# POWER.net
KiCad netlist of a schematic drawn in Altium Designer
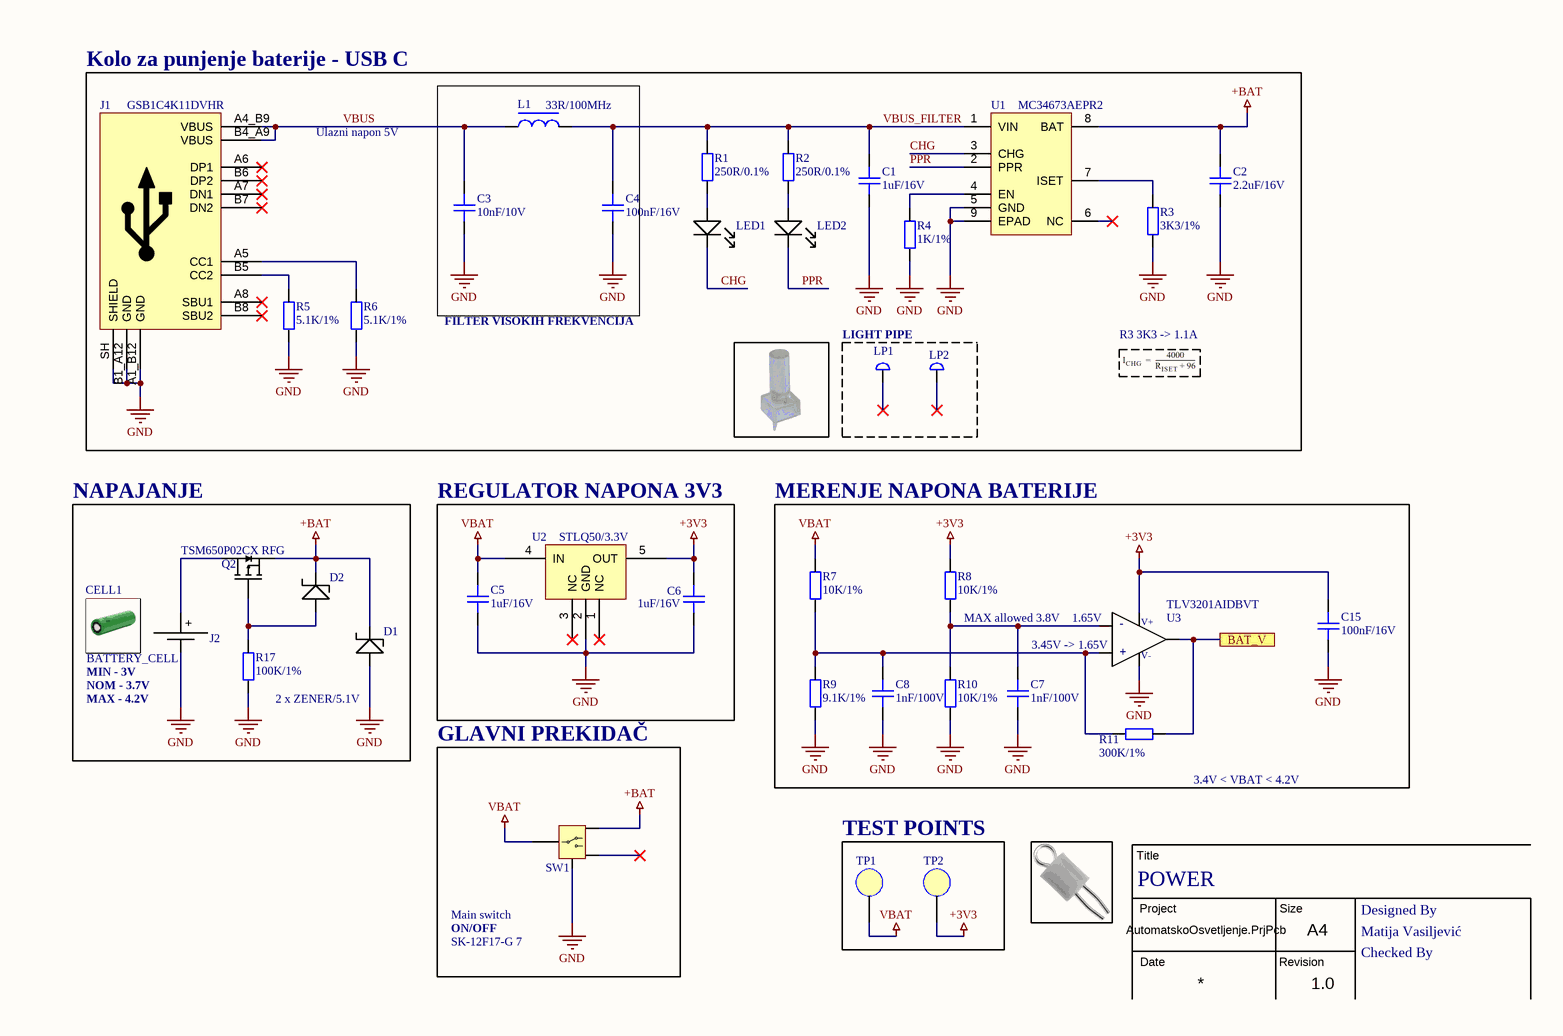
[diagram p0: POWER.SchDoc]

(export (version "E")
  (design (tool "Eeschema 10.0.6"))
  (components
    (comp (ref "C1")
      (value "1uF/16V")
      (footprint "CAP_0603")
      (description "1 µF ±5% 16V Ceramic Capacitor X7R 0603 (1608 Metric)")
      (fields (field (name "MPN") "0603YC105JAT2A"))
      (libsource (lib "Library-AutomatskoOsvetljenje") (part "1uF/16V"))
    )
    (comp (ref "C2")
      (value "2.2uF/16V")
      (footprint "CAP_0603")
      (description "2.2 µF ±10% 16V Ceramic Capacitor X7S 0603 (1608 Metric)")
      (fields (field (name "MPN") "GRM188C71C225KE11D"))
      (libsource (lib "Library-AutomatskoOsvetljenje") (part "2.2uF/16V"))
    )
    (comp (ref "C3")
      (value "10nF/10V")
      (footprint "CAP_0603")
      (description "10000 pF ±10% 50V Ceramic Capacitor X7R 0603 (1608 Metric)")
      (fields (field (name "MPN") "0603B103K500CT"))
      (libsource (lib "Library-AutomatskoOsvetljenje") (part "10nF/10V"))
    )
    (comp (ref "C4")
      (value "100nF/16V")
      (footprint "CAP_0603")
      (description "0.1 µF ±10% 16V Ceramic Capacitor X7R 0603 (1608 Metric)")
      (fields (field (name "MPN") "CC0603KRX7R7BB104"))
      (libsource (lib "Library-AutomatskoOsvetljenje") (part "100nF/16V"))
    )
    (comp (ref "C5")
      (value "1uF/16V")
      (footprint "CAP_0603")
      (description "1 µF ±5% 16V Ceramic Capacitor X7R 0603 (1608 Metric)")
      (fields (field (name "MPN") "0603YC105JAT2A"))
      (libsource (lib "Library-AutomatskoOsvetljenje") (part "1uF/16V"))
    )
    (comp (ref "C6")
      (value "1uF/16V")
      (footprint "CAP_0603")
      (description "1 µF ±5% 16V Ceramic Capacitor X7R 0603 (1608 Metric)")
      (fields (field (name "MPN") "0603YC105JAT2A"))
      (libsource (lib "Library-AutomatskoOsvetljenje") (part "1uF/16V"))
    )
    (comp (ref "C7")
      (value "1nF/100V")
      (footprint "CAP_0603")
      (description "1 µF ±10% 10V Ceramic Capacitor X7R 0603 (1608 Metric)")
      (fields (field (name "MPN") "CL10B105KP8NNNC"))
      (libsource (lib "Library-AutomatskoOsvetljenje") (part "1nF/100V"))
    )
    (comp (ref "C8")
      (value "1nF/100V")
      (footprint "CAP_0603")
      (description "1 µF ±10% 10V Ceramic Capacitor X7R 0603 (1608 Metric)")
      (fields (field (name "MPN") "CL10B105KP8NNNC"))
      (libsource (lib "Library-AutomatskoOsvetljenje") (part "1nF/100V"))
    )
    (comp (ref "C15")
      (value "100nF/16V")
      (footprint "CAP_0603")
      (description "0.1 µF ±10% 16V Ceramic Capacitor X7R 0603 (1608 Metric)")
      (fields (field (name "MPN") "CC0603KRX7R7BB104"))
      (libsource (lib "Library-AutomatskoOsvetljenje") (part "100nF/16V"))
    )
    (comp (ref "CELL1")
      (value "BATTERY_CELL")
      (description "CELL 18650 SAMSUNG 3200mAh")
      (libsource (lib "Library-AutomatskoOsvetljenje") (part "BATTERY_CELL"))
    )
    (comp (ref "D1")
      (value "ZENER/5.1V")
      (footprint "ZENER_SMA")
      (description "Zener Diode 5.1 V 1.5 W ±5% Surface Mount SMA")
      (fields (field (name "MPN") "1SMA5918BT3G"))
      (libsource (lib "Library-AutomatskoOsvetljenje") (part "ZENER/5.1V"))
    )
    (comp (ref "D2")
      (value "2 x ZENER/5.1V")
      (footprint "ZENER_SMA")
      (description "Zener Diode 5.1 V 1.5 W ±5% Surface Mount SMA")
      (fields (field (name "MPN") "1SMA5918BT3G"))
      (libsource (lib "Library-AutomatskoOsvetljenje") (part "ZENER/5.1V"))
    )
    (comp (ref "J1")
      (value "GSB1C4K11DVHR")
      (footprint "USBC_GSB1C4K11DVHR")
      (description "USB-C (USB TYPE-C) USB 2.0 Receptacle Connector 24 (16+8 Dummy) Position Through Hole, Right Angle")
      (libsource (lib "Library-AutomatskoOsvetljenje") (part "USB_C_GSB1C4K11DVHR"))
    )
    (comp (ref "J2")
      (value "12BHC186CLP-GR")
      (footprint "BATTERY_HOLDER_18650")
      (description "Cylindrical Battery Contacts, Clips, Holders & Springs 18650 Holder Board Mount Clip")
      (libsource (lib "Library-AutomatskoOsvetljenje") (part "BATTERY_HOLDER_18650"))
    )
    (comp (ref "L1")
      (value "33R/100MHz")
      (footprint "INDC_0603")
      (description "33 Ohms @ 100 MHz 1 Power Line Ferrite Bead 0603 (1608 Metric) 3A 25mOhm")
      (fields (field (name "MPN") "BLM18PG330SN1DBLM18PG330SN1D"))
      (libsource (lib "Library-AutomatskoOsvetljenje") (part "33R/100MHz"))
    )
    (comp (ref "LED1")
      (value "150060RS75000")
      (footprint "LED_0603")
      (description "Red 625nm LED Indication - Discrete 2V 0603 (1608 Metric)")
      (libsource (lib "Library-AutomatskoOsvetljenje") (part "INDICATION_LED_RED_1500_1"))
    )
    (comp (ref "LED2")
      (value "150060VS75000")
      (footprint "LED_0603")
      (description "Green 570nm LED Indication - Discrete 2V 0603 (1608 Metric)")
      (libsource (lib "Library-AutomatskoOsvetljenje") (part "INDICATION_LED_GREEN_1500"))
    )
    (comp (ref "LP1")
      (value "LIGHT_PIPE")
      (footprint "LIGHT_PIPE_VLP-400-F")
      (description "Light pipe for indication led")
      (fields (field (name "MPN") "VLP-400-F"))
      (libsource (lib "Library-AutomatskoOsvetljenje") (part "LIGHT_PIPE"))
    )
    (comp (ref "LP2")
      (value "LIGHT_PIPE")
      (footprint "LIGHT_PIPE_VLP-400-F")
      (description "Light pipe for indication led")
      (fields (field (name "MPN") "VLP-400-F"))
      (libsource (lib "Library-AutomatskoOsvetljenje") (part "LIGHT_PIPE"))
    )
    (comp (ref "Q2")
      (value "TSM650P02CX RFG")
      (footprint "SOT23-3")
      (description "P-Channel 20 V 4.1A (Tc) 1.56W (Tc) Surface Mount SOT-23")
      (libsource (lib "Library-AutomatskoOsvetljenje") (part "TSM650P02CX RFG PMOS"))
    )
    (comp (ref "R1")
      (value "250R/0.1%")
      (footprint "RES_0603")
      (description "250 Ohms ±0.1% 0.1W, 1/10W Chip Resistor 0603 (1608 Metric) Thin Film")
      (fields (field (name "MPN") "RT0603BRE07250RL"))
      (libsource (lib "Library-AutomatskoOsvetljenje") (part "250R/0.1%"))
    )
    (comp (ref "R2")
      (value "250R/0.1%")
      (footprint "RES_0603")
      (description "250 Ohms ±0.1% 0.1W, 1/10W Chip Resistor 0603 (1608 Metric) Thin Film")
      (fields (field (name "MPN") "RT0603BRE07250RL"))
      (libsource (lib "Library-AutomatskoOsvetljenje") (part "250R/0.1%"))
    )
    (comp (ref "R3")
      (value "3K3/1%")
      (footprint "RES_0603")
      (description "3.3 kOhms ±1% 0.1W, 1/10W Chip Resistor 0603 (1608 Metric) Automotive AEC-Q200 Thick Film")
      (fields (field (name "MPN") "RMCF0603FT3K30"))
      (libsource (lib "Library-AutomatskoOsvetljenje") (part "3K3/1%"))
    )
    (comp (ref "R4")
      (value "1K/1%")
      (footprint "RES_0603")
      (description "1 kOhms ±1% 0.1W, 1/10W Chip Resistor 0603 (1608 Metric) Moisture Resistant Thick Film")
      (fields (field (name "MPN") "RC0603FR-071KL"))
      (libsource (lib "Library-AutomatskoOsvetljenje") (part "1K/1%"))
    )
    (comp (ref "R5")
      (value "5.1K/1%")
      (footprint "RES_0603")
      (description "5.1 kOhms ±1% 0.1W, 1/10W Chip Resistor 0603 (1608 Metric) Moisture Resistant Thick Film")
      (fields (field (name "MPN") "RC0603FR-075K1L"))
      (libsource (lib "Library-AutomatskoOsvetljenje") (part "5.1K/1%"))
    )
    (comp (ref "R6")
      (value "5.1K/1%")
      (footprint "RES_0603")
      (description "5.1 kOhms ±1% 0.1W, 1/10W Chip Resistor 0603 (1608 Metric) Moisture Resistant Thick Film")
      (fields (field (name "MPN") "RC0603FR-075K1L"))
      (libsource (lib "Library-AutomatskoOsvetljenje") (part "5.1K/1%"))
    )
    (comp (ref "R7")
      (value "10K/1%")
      (footprint "RES_0603")
      (description "10 kOhms ±1% 0.1W, 1/10W Chip Resistor 0603 (1608 Metric) Moisture Resistant Thick Film")
      (fields (field (name "MPN") "CR0603-FX-1002ELF"))
      (libsource (lib "Library-AutomatskoOsvetljenje") (part "10K/1%"))
    )
    (comp (ref "R8")
      (value "10K/1%")
      (footprint "RES_0603")
      (description "10 kOhms ±1% 0.1W, 1/10W Chip Resistor 0603 (1608 Metric) Moisture Resistant Thick Film")
      (fields (field (name "MPN") "CR0603-FX-1002ELF"))
      (libsource (lib "Library-AutomatskoOsvetljenje") (part "10K/1%"))
    )
    (comp (ref "R9")
      (value "9.1K/1%")
      (footprint "RES_0603")
      (description "9.1 kOhms ±1% 0.1W, 1/10W Chip Resistor 0603 (1608 Metric) Thick Film")
      (fields (field (name "MPN") "CRCW06039K10FKEAC"))
      (libsource (lib "Library-AutomatskoOsvetljenje") (part "9.1K/1%"))
    )
    (comp (ref "R10")
      (value "10K/1%")
      (footprint "RES_0603")
      (description "10 kOhms ±1% 0.1W, 1/10W Chip Resistor 0603 (1608 Metric) Moisture Resistant Thick Film")
      (fields (field (name "MPN") "CR0603-FX-1002ELF"))
      (libsource (lib "Library-AutomatskoOsvetljenje") (part "10K/1%"))
    )
    (comp (ref "R11")
      (value "300K/1%")
      (footprint "RES_0603")
      (description "300 kOhms ±1% 0.1W, 1/10W Chip Resistor 0603 (1608 Metric) Automotive AEC-Q200 Thick Film")
      (fields (field (name "MPN") "RMCF0603FT300K"))
      (libsource (lib "Library-AutomatskoOsvetljenje") (part "300K/1%"))
    )
    (comp (ref "R17")
      (value "100K/1%")
      (footprint "RES_0603")
      (description "100 kOhms ±1% 0.1W, 1/10W Chip Resistor 0603 (1608 Metric) Automotive AEC-Q200 Thick Film")
      (fields (field (name "MPN") "ERJ-3EKF1003V"))
      (libsource (lib "Library-AutomatskoOsvetljenje") (part "100K/1%"))
    )
    (comp (ref "SW1")
      (value "SK-12F17-G 7")
      (footprint "SWITCH_SK-12F17-G_HORIZONTAL")
      (description "SWITCH SLIDE SPDT 300MA 30V")
      (libsource (lib "Symbols") (part "SWITCH_MAIN"))
    )
    (comp (ref "TP1")
      (value "TESTPOINT")
      (footprint "TESTPOINT")
      (description "White PC Test Point, Miniature Phosphor Bronze Silver Plating Through Hole Mounting Type")
      (fields (field (name "MPN") "5002"))
      (libsource (lib "Library-AutomatskoOsvetljenje") (part "TESTPOINT"))
    )
    (comp (ref "TP2")
      (value "TESTPOINT")
      (footprint "TESTPOINT")
      (description "White PC Test Point, Miniature Phosphor Bronze Silver Plating Through Hole Mounting Type")
      (fields (field (name "MPN") "5002"))
      (libsource (lib "Library-AutomatskoOsvetljenje") (part "TESTPOINT"))
    )
    (comp (ref "U1")
      (value "MC34673AEPR2")
      (footprint "UDFN 8")
      (description "Charger IC Lithium Ion/Polymer 8-UDFN (3x2)")
      (libsource (lib "Library-AutomatskoOsvetljenje") (part "MC34673AEPR2"))
    )
    (comp (ref "U2")
      (value "STLQ50/3.3V")
      (footprint "SOT323-5")
      (description "IC REG LINEAR 3.3V 50MA SOT323-5")
      (fields (field (name "MPN") "STLQ50C33R"))
      (libsource (lib "Library-AutomatskoOsvetljenje") (part "REG-STLQ50/3.3V"))
    )
    (comp (ref "U3")
      (value "TLV3201AIDBVT")
      (footprint "SOT23-5")
      (description "Comparator General Purpose Push-Pull SOT-23-5")
      (libsource (lib "Library-AutomatskoOsvetljenje") (part "TLV3201AIDBVT_COMPARATOR"))
    )
  )
  (nets
    (net (code "1") (name "+3V3") (class "Default")
      (node (ref "C15") (pin "2") (pinfunction "2_2") (pintype "passive"))
      (node (ref "C6") (pin "2") (pinfunction "2_2") (pintype "passive"))
      (node (ref "R8") (pin "2") (pinfunction "2_2") (pintype "passive"))
      (node (ref "TP2") (pin "1") (pinfunction "TP_1") (pintype "passive"))
      (node (ref "U2") (pin "5") (pinfunction "OUT_5") (pintype "passive"))
      (node (ref "U3") (pin "5") (pinfunction "+VDD_5") (pintype "passive"))
    )
    (net (code "2") (name "+BAT") (class "Default")
      (node (ref "C2") (pin "2") (pinfunction "2_2") (pintype "passive"))
      (node (ref "D1") (pin "2") (pinfunction "Cathode_2") (pintype "passive"))
      (node (ref "D2") (pin "2") (pinfunction "Cathode_2") (pintype "passive"))
      (node (ref "Q2") (pin "2") (pinfunction "2_2") (pintype "passive"))
      (node (ref "SW1") (pin "3") (pinfunction "3T_3") (pintype "passive"))
      (node (ref "U1") (pin "8") (pinfunction "BAT_8") (pintype "passive"))
    )
    (net (code "3") (name "/BAT_V") (class "Default")
      (node (ref "R11") (pin "2") (pinfunction "2_2") (pintype "passive"))
      (node (ref "U3") (pin "1") (pinfunction "OUT_1") (pintype "passive"))
    )
    (net (code "4") (name "/CHG") (class "Default")
      (node (ref "LED1") (pin "2") (pinfunction "Cathode_2") (pintype "passive"))
      (node (ref "U1") (pin "3") (pinfunction "CHG_3") (pintype "passive"))
    )
    (net (code "5") (name "/PPR") (class "Default")
      (node (ref "LED2") (pin "2") (pinfunction "Cathode_2") (pintype "passive"))
      (node (ref "U1") (pin "2") (pinfunction "PPR_2") (pintype "passive"))
    )
    (net (code "6") (name "/VBUS") (class "Default")
      (node (ref "C3") (pin "2") (pinfunction "2_2") (pintype "passive"))
      (node (ref "J1") (pin "A4_B9") (pinfunction "VBUS_A4_B9") (pintype "passive"))
      (node (ref "J1") (pin "B4_A9") (pinfunction "VBUS_B4_A9") (pintype "passive"))
      (node (ref "L1") (pin "1") (pinfunction "1_1") (pintype "passive"))
    )
    (net (code "7") (name "/VBUS_FILTER") (class "Default")
      (node (ref "C1") (pin "2") (pinfunction "2_2") (pintype "passive"))
      (node (ref "C4") (pin "2") (pinfunction "2_2") (pintype "passive"))
      (node (ref "L1") (pin "2") (pinfunction "2_2") (pintype "passive"))
      (node (ref "R1") (pin "2") (pinfunction "2_2") (pintype "passive"))
      (node (ref "R2") (pin "2") (pinfunction "2_2") (pintype "passive"))
      (node (ref "U1") (pin "1") (pinfunction "VIN_1") (pintype "passive"))
    )
    (net (code "8") (name "GND") (class "Default")
      (node (ref "C1") (pin "1") (pinfunction "1_1") (pintype "passive"))
      (node (ref "C15") (pin "1") (pinfunction "1_1") (pintype "passive"))
      (node (ref "C2") (pin "1") (pinfunction "1_1") (pintype "passive"))
      (node (ref "C3") (pin "1") (pinfunction "1_1") (pintype "passive"))
      (node (ref "C4") (pin "1") (pinfunction "1_1") (pintype "passive"))
      (node (ref "C5") (pin "1") (pinfunction "1_1") (pintype "passive"))
      (node (ref "C6") (pin "1") (pinfunction "1_1") (pintype "passive"))
      (node (ref "C7") (pin "1") (pinfunction "1_1") (pintype "passive"))
      (node (ref "C8") (pin "1") (pinfunction "1_1") (pintype "passive"))
      (node (ref "D1") (pin "1") (pinfunction "Anode_1") (pintype "passive"))
      (node (ref "J1") (pin "A1_B12") (pinfunction "GND_A1_B12") (pintype "passive"))
      (node (ref "J1") (pin "B1_A12") (pinfunction "GND_B1_A12") (pintype "passive"))
      (node (ref "J1") (pin "SH") (pinfunction "SHIELD_SH") (pintype "passive"))
      (node (ref "J2") (pin "2") (pinfunction "-_2") (pintype "passive"))
      (node (ref "R10") (pin "1") (pinfunction "1_1") (pintype "passive"))
      (node (ref "R17") (pin "1") (pinfunction "1_1") (pintype "passive"))
      (node (ref "R3") (pin "1") (pinfunction "1_1") (pintype "passive"))
      (node (ref "R4") (pin "1") (pinfunction "1_1") (pintype "passive"))
      (node (ref "R5") (pin "1") (pinfunction "1_1") (pintype "passive"))
      (node (ref "R6") (pin "1") (pinfunction "1_1") (pintype "passive"))
      (node (ref "R9") (pin "1") (pinfunction "1_1") (pintype "passive"))
      (node (ref "SW1") (pin "4") (pinfunction "GND_4") (pintype "passive"))
      (node (ref "U1") (pin "5") (pinfunction "GND_5") (pintype "passive"))
      (node (ref "U1") (pin "9") (pinfunction "EPAD_9") (pintype "passive"))
      (node (ref "U2") (pin "2") (pinfunction "GND_2") (pintype "passive"))
      (node (ref "U3") (pin "2") (pinfunction "-VDD_2") (pintype "passive"))
    )
    (net (code "9") (name "Net-(D2-Anode)") (class "Default")
      (node (ref "D2") (pin "1") (pinfunction "Anode_1") (pintype "passive"))
      (node (ref "Q2") (pin "1") (pinfunction "1_1") (pintype "passive"))
      (node (ref "R17") (pin "2") (pinfunction "2_2") (pintype "passive"))
    )
    (net (code "10") (name "Net-(J1-CC1)") (class "Default")
      (node (ref "J1") (pin "A5") (pinfunction "CC1_A5") (pintype "passive"))
      (node (ref "R6") (pin "2") (pinfunction "2_2") (pintype "passive"))
    )
    (net (code "11") (name "Net-(J1-CC2)") (class "Default")
      (node (ref "J1") (pin "B5") (pinfunction "CC2_B5") (pintype "passive"))
      (node (ref "R5") (pin "2") (pinfunction "2_2") (pintype "passive"))
    )
    (net (code "12") (name "Net-(J2-+)") (class "Default")
      (node (ref "J2") (pin "1") (pinfunction "+_1") (pintype "passive"))
      (node (ref "Q2") (pin "3") (pinfunction "3_3") (pintype "passive"))
    )
    (net (code "13") (name "Net-(LED1-Anode)") (class "Default")
      (node (ref "LED1") (pin "1") (pinfunction "Anode_1") (pintype "passive"))
      (node (ref "R1") (pin "1") (pinfunction "1_1") (pintype "passive"))
    )
    (net (code "14") (name "Net-(LED2-Anode)") (class "Default")
      (node (ref "LED2") (pin "1") (pinfunction "Anode_1") (pintype "passive"))
      (node (ref "R2") (pin "1") (pinfunction "1_1") (pintype "passive"))
    )
    (net (code "15") (name "Net-(U1-EN)") (class "Default")
      (node (ref "R4") (pin "2") (pinfunction "2_2") (pintype "passive"))
      (node (ref "U1") (pin "4") (pinfunction "EN_4") (pintype "passive"))
    )
    (net (code "16") (name "Net-(U1-ISET)") (class "Default")
      (node (ref "R3") (pin "2") (pinfunction "2_2") (pintype "passive"))
      (node (ref "U1") (pin "7") (pinfunction "ISET_7") (pintype "passive"))
    )
    (net (code "17") (name "Net-(U3-+)") (class "Default")
      (node (ref "C8") (pin "2") (pinfunction "2_2") (pintype "passive"))
      (node (ref "R11") (pin "1") (pinfunction "1_1") (pintype "passive"))
      (node (ref "R7") (pin "1") (pinfunction "1_1") (pintype "passive"))
      (node (ref "R9") (pin "2") (pinfunction "2_2") (pintype "passive"))
      (node (ref "U3") (pin "3") (pinfunction "+_3") (pintype "passive"))
    )
    (net (code "18") (name "Net-(U3--)") (class "Default")
      (node (ref "C7") (pin "2") (pinfunction "2_2") (pintype "passive"))
      (node (ref "R10") (pin "2") (pinfunction "2_2") (pintype "passive"))
      (node (ref "R8") (pin "1") (pinfunction "1_1") (pintype "passive"))
      (node (ref "U3") (pin "4") (pinfunction "-_4") (pintype "passive"))
    )
    (net (code "19") (name "VBAT") (class "Default")
      (node (ref "C5") (pin "2") (pinfunction "2_2") (pintype "passive"))
      (node (ref "R7") (pin "2") (pinfunction "2_2") (pintype "passive"))
      (node (ref "SW1") (pin "1") (pinfunction "1P_1") (pintype "passive"))
      (node (ref "TP1") (pin "1") (pinfunction "TP_1") (pintype "passive"))
      (node (ref "U2") (pin "4") (pinfunction "IN_4") (pintype "passive"))
    )
    (net (code "20") (name "unconnected-(J1-DN1-PadA7)") (class "Default")
      (node (ref "J1") (pin "A7") (pinfunction "DN1_A7") (pintype "passive+no_connect"))
    )
    (net (code "21") (name "unconnected-(J1-DN2-PadB7)") (class "Default")
      (node (ref "J1") (pin "B7") (pinfunction "DN2_B7") (pintype "passive+no_connect"))
    )
    (net (code "22") (name "unconnected-(J1-DP1-PadA6)") (class "Default")
      (node (ref "J1") (pin "A6") (pinfunction "DP1_A6") (pintype "passive+no_connect"))
    )
    (net (code "23") (name "unconnected-(J1-DP2-PadB6)") (class "Default")
      (node (ref "J1") (pin "B6") (pinfunction "DP2_B6") (pintype "passive+no_connect"))
    )
    (net (code "24") (name "unconnected-(J1-SBU1-PadA8)") (class "Default")
      (node (ref "J1") (pin "A8") (pinfunction "SBU1_A8") (pintype "passive+no_connect"))
    )
    (net (code "25") (name "unconnected-(J1-SBU2-PadB8)") (class "Default")
      (node (ref "J1") (pin "B8") (pinfunction "SBU2_B8") (pintype "passive+no_connect"))
    )
    (net (code "26") (name "unconnected-(LP1-Pad1)") (class "Default")
      (node (ref "LP1") (pin "1") (pinfunction "1_1") (pintype "passive+no_connect"))
    )
    (net (code "27") (name "unconnected-(LP2-Pad1)") (class "Default")
      (node (ref "LP2") (pin "1") (pinfunction "1_1") (pintype "passive+no_connect"))
    )
    (net (code "28") (name "unconnected-(SW1-2T-Pad2)") (class "Default")
      (node (ref "SW1") (pin "2") (pinfunction "2T_2") (pintype "passive+no_connect"))
    )
    (net (code "29") (name "unconnected-(U1-NC-Pad6)") (class "Default")
      (node (ref "U1") (pin "6") (pinfunction "NC_6") (pintype "passive+no_connect"))
    )
    (net (code "30") (name "unconnected-(U2-NC-Pad1)") (class "Default")
      (node (ref "U2") (pin "1") (pinfunction "NC_1") (pintype "passive+no_connect"))
    )
    (net (code "31") (name "unconnected-(U2-NC-Pad3)") (class "Default")
      (node (ref "U2") (pin "3") (pinfunction "NC_3") (pintype "passive+no_connect"))
    )
  )
)
